# Channel.net
KiCad netlist of a schematic drawn in Altium Designer
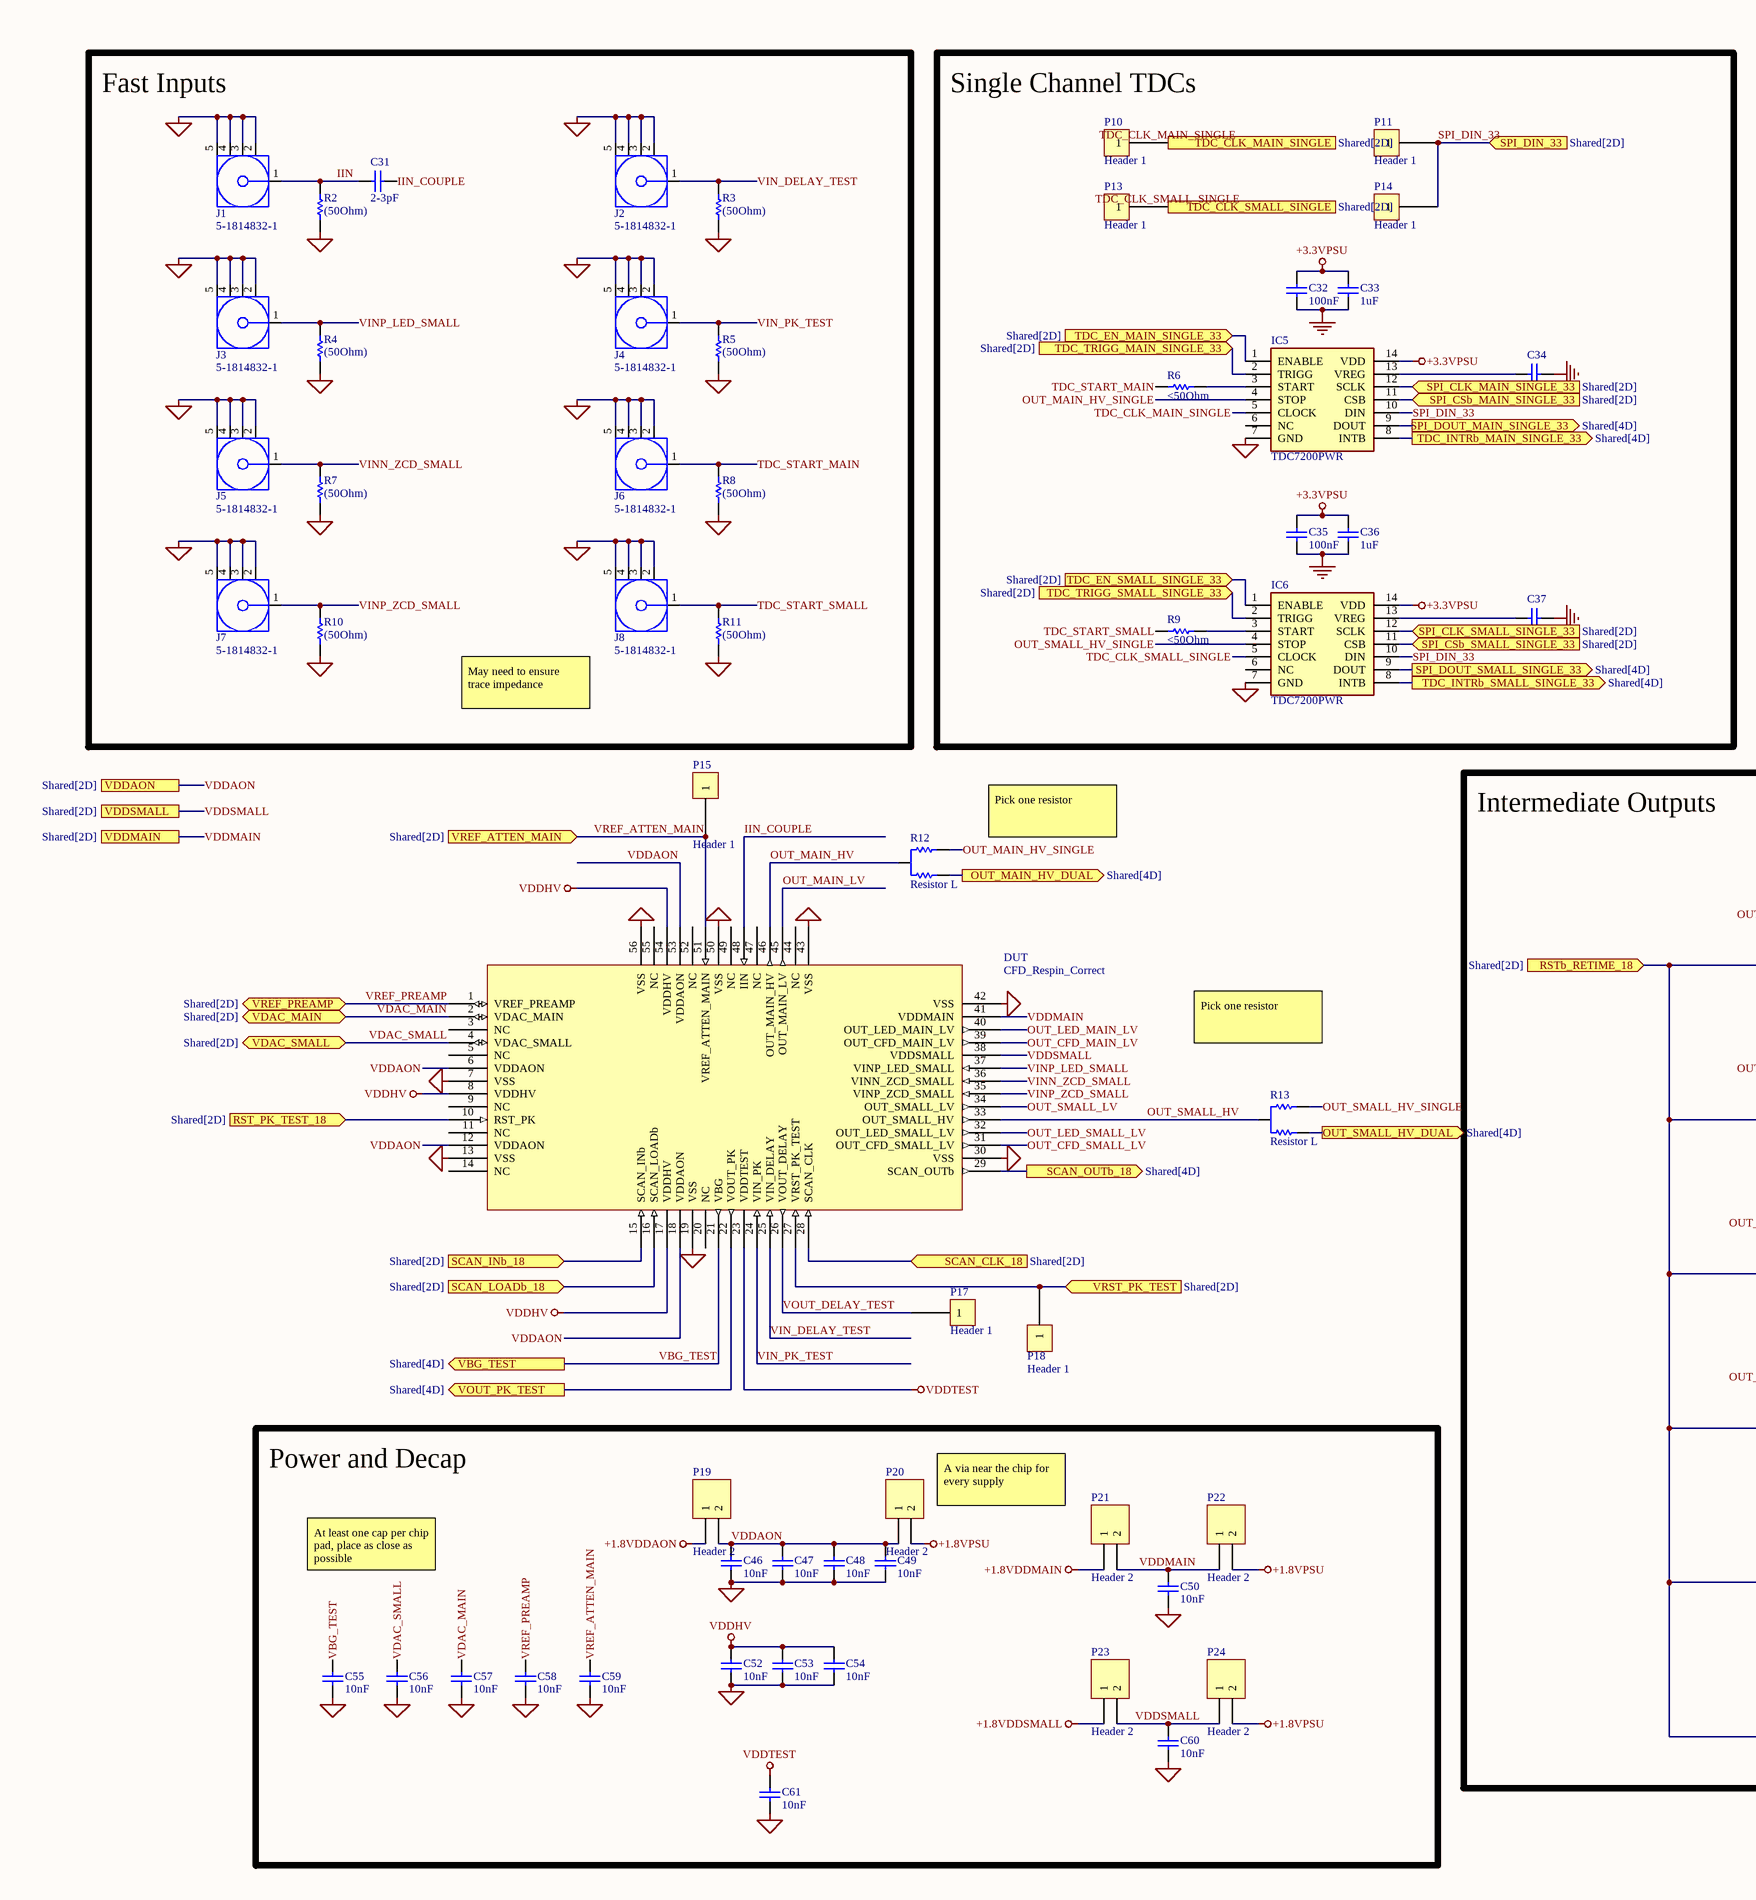
[diagram p0: Channel.SchDoc, left]
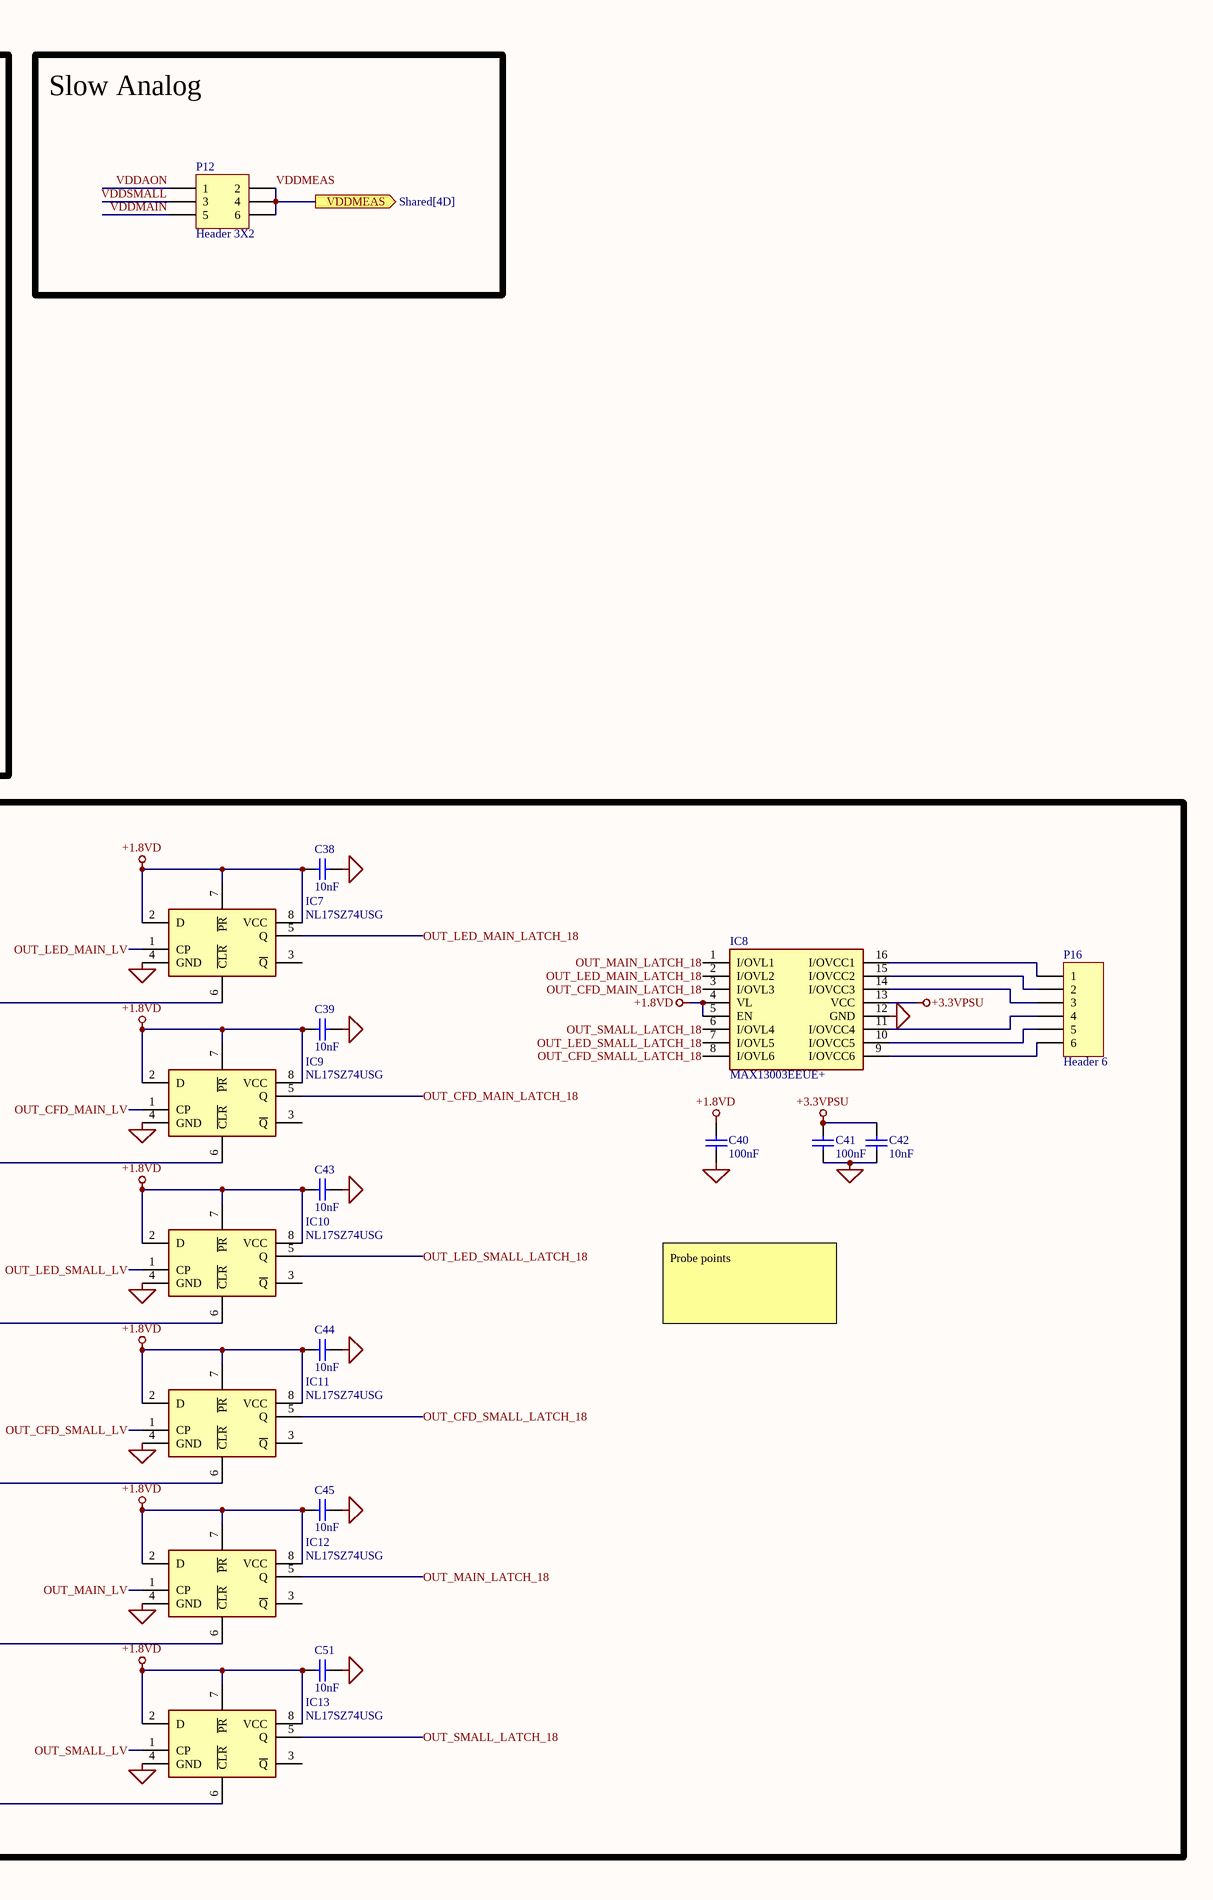
[diagram p1: Channel.SchDoc, right]

(export (version "E")
  (design (tool "Eeschema 10.0.6"))
  (components
    (comp (ref "C31")
      (value "2-3pF")
      (footprint "CAPC1608X90X35ML10T15")
      (description "0603,2-3pF")
      (fields (field (name "MANUFACTURER") "Murata"))
      (libsource (lib "Altium Content Vault") (part "CAP-NP-2"))
    )
    (comp (ref "C32")
      (value "100nF")
      (footprint "CAPC1608X90X35ML10T15")
      (description "0603,100nF")
      (fields (field (name "MANUFACTURER") "Murata"))
      (libsource (lib "Altium Content Vault") (part "CAP-NP-2"))
    )
    (comp (ref "C33")
      (value "1uF")
      (footprint "CAPC1608X90X35ML10T15")
      (description "0603,1uF")
      (fields (field (name "MANUFACTURER") "Murata"))
      (libsource (lib "Altium Content Vault") (part "CAP-NP-2"))
    )
    (comp (ref "C34")
      (value "1uF")
      (footprint "CAPC1608X90X35ML10T15")
      (description "0603,1uF")
      (fields (field (name "MANUFACTURER") "Murata"))
      (libsource (lib "Altium Content Vault") (part "CAP-NP-2"))
    )
    (comp (ref "C35")
      (value "100nF")
      (footprint "CAPC1608X90X35ML10T15")
      (description "0603,100nF")
      (fields (field (name "MANUFACTURER") "Murata"))
      (libsource (lib "Altium Content Vault") (part "CAP-NP-2"))
    )
    (comp (ref "C36")
      (value "1uF")
      (footprint "CAPC1608X90X35ML10T15")
      (description "0603,1uF")
      (fields (field (name "MANUFACTURER") "Murata"))
      (libsource (lib "Altium Content Vault") (part "CAP-NP-2"))
    )
    (comp (ref "C37")
      (value "1uF")
      (footprint "CAPC1608X90X35ML10T15")
      (description "0603,1uF")
      (fields (field (name "MANUFACTURER") "Murata"))
      (libsource (lib "Altium Content Vault") (part "CAP-NP-2"))
    )
    (comp (ref "C38")
      (value "10nF")
      (footprint "CAPC1608X90X35ML10T15")
      (description "0603,10nF")
      (fields (field (name "MANUFACTURER") "Murata"))
      (libsource (lib "Altium Content Vault") (part "CAP-NP-2"))
    )
    (comp (ref "C39")
      (value "10nF")
      (footprint "CAPC1608X90X35ML10T15")
      (description "0603,10nF")
      (fields (field (name "MANUFACTURER") "Murata"))
      (libsource (lib "Altium Content Vault") (part "CAP-NP-2"))
    )
    (comp (ref "C40")
      (value "100nF")
      (footprint "CAPC1608X90X35ML10T15")
      (description "0603,100nF")
      (fields (field (name "MANUFACTURER") "Murata"))
      (libsource (lib "Altium Content Vault") (part "CAP-NP-2"))
    )
    (comp (ref "C41")
      (value "100nF")
      (footprint "CAPC1608X90X35ML10T15")
      (description "0603,100nF")
      (fields (field (name "MANUFACTURER") "Murata"))
      (libsource (lib "Altium Content Vault") (part "CAP-NP-2"))
    )
    (comp (ref "C42")
      (value "10nF")
      (footprint "CAPC1608X90X35ML10T15")
      (description "0603,10nF")
      (fields (field (name "MANUFACTURER") "Murata"))
      (libsource (lib "Altium Content Vault") (part "CAP-NP-2"))
    )
    (comp (ref "C43")
      (value "10nF")
      (footprint "CAPC1608X90X35ML10T15")
      (description "0603,10nF")
      (fields (field (name "MANUFACTURER") "Murata"))
      (libsource (lib "Altium Content Vault") (part "CAP-NP-2"))
    )
    (comp (ref "C44")
      (value "10nF")
      (footprint "CAPC1608X90X35ML10T15")
      (description "0603,10nF")
      (fields (field (name "MANUFACTURER") "Murata"))
      (libsource (lib "Altium Content Vault") (part "CAP-NP-2"))
    )
    (comp (ref "C45")
      (value "10nF")
      (footprint "CAPC1608X90X35ML10T15")
      (description "0603,10nF")
      (fields (field (name "MANUFACTURER") "Murata"))
      (libsource (lib "Altium Content Vault") (part "CAP-NP-2"))
    )
    (comp (ref "C46")
      (value "10nF")
      (footprint "CAPC1608X90X35ML10T15")
      (description "0603,10nF")
      (fields (field (name "MANUFACTURER") "Murata"))
      (libsource (lib "Altium Content Vault") (part "CAP-NP-2"))
    )
    (comp (ref "C47")
      (value "10nF")
      (footprint "CAPC1608X90X35ML10T15")
      (description "0603,10nF")
      (fields (field (name "MANUFACTURER") "Murata"))
      (libsource (lib "Altium Content Vault") (part "CAP-NP-2"))
    )
    (comp (ref "C48")
      (value "10nF")
      (footprint "CAPC1608X90X35ML10T15")
      (description "0603,10nF")
      (fields (field (name "MANUFACTURER") "Murata"))
      (libsource (lib "Altium Content Vault") (part "CAP-NP-2"))
    )
    (comp (ref "C49")
      (value "10nF")
      (footprint "CAPC1608X90X35ML10T15")
      (description "0603,10nF")
      (fields (field (name "MANUFACTURER") "Murata"))
      (libsource (lib "Altium Content Vault") (part "CAP-NP-2"))
    )
    (comp (ref "C50")
      (value "10nF")
      (footprint "CAPC1608X90X35ML10T15")
      (description "0603,10nF")
      (fields (field (name "MANUFACTURER") "Murata"))
      (libsource (lib "Altium Content Vault") (part "CAP-NP-2"))
    )
    (comp (ref "C51")
      (value "10nF")
      (footprint "CAPC1608X90X35ML10T15")
      (description "0603,10nF")
      (fields (field (name "MANUFACTURER") "Murata"))
      (libsource (lib "Altium Content Vault") (part "CAP-NP-2"))
    )
    (comp (ref "C52")
      (value "10nF")
      (footprint "CAPC1608X90X35ML10T15")
      (description "0603,10nF")
      (fields (field (name "MANUFACTURER") "Murata"))
      (libsource (lib "Altium Content Vault") (part "CAP-NP-2"))
    )
    (comp (ref "C53")
      (value "10nF")
      (footprint "CAPC1608X90X35ML10T15")
      (description "0603,10nF")
      (fields (field (name "MANUFACTURER") "Murata"))
      (libsource (lib "Altium Content Vault") (part "CAP-NP-2"))
    )
    (comp (ref "C54")
      (value "10nF")
      (footprint "CAPC1608X90X35ML10T15")
      (description "0603,10nF")
      (fields (field (name "MANUFACTURER") "Murata"))
      (libsource (lib "Altium Content Vault") (part "CAP-NP-2"))
    )
    (comp (ref "C55")
      (value "10nF")
      (footprint "CAPC1608X90X35ML10T15")
      (description "0603,10nF")
      (fields (field (name "MANUFACTURER") "Murata"))
      (libsource (lib "Altium Content Vault") (part "CAP-NP-2"))
    )
    (comp (ref "C56")
      (value "10nF")
      (footprint "CAPC1608X90X35ML10T15")
      (description "0603,10nF")
      (fields (field (name "MANUFACTURER") "Murata"))
      (libsource (lib "Altium Content Vault") (part "CAP-NP-2"))
    )
    (comp (ref "C57")
      (value "10nF")
      (footprint "CAPC1608X90X35ML10T15")
      (description "0603,10nF")
      (fields (field (name "MANUFACTURER") "Murata"))
      (libsource (lib "Altium Content Vault") (part "CAP-NP-2"))
    )
    (comp (ref "C58")
      (value "10nF")
      (footprint "CAPC1608X90X35ML10T15")
      (description "0603,10nF")
      (fields (field (name "MANUFACTURER") "Murata"))
      (libsource (lib "Altium Content Vault") (part "CAP-NP-2"))
    )
    (comp (ref "C59")
      (value "10nF")
      (footprint "CAPC1608X90X35ML10T15")
      (description "0603,10nF")
      (fields (field (name "MANUFACTURER") "Murata"))
      (libsource (lib "Altium Content Vault") (part "CAP-NP-2"))
    )
    (comp (ref "C60")
      (value "10nF")
      (footprint "CAPC1608X90X35ML10T15")
      (description "0603,10nF")
      (fields (field (name "MANUFACTURER") "Murata"))
      (libsource (lib "Altium Content Vault") (part "CAP-NP-2"))
    )
    (comp (ref "C61")
      (value "10nF")
      (footprint "CAPC1608X90X35ML10T15")
      (description "0603,10nF")
      (fields (field (name "MANUFACTURER") "Murata"))
      (libsource (lib "Altium Content Vault") (part "CAP-NP-2"))
    )
    (comp (ref "DUT")
      (value "CFD_Respin_Correct")
      (footprint "QFN50P800X800X80_HS-57N_WIDEVIAS")
      (libsource (lib "intlib") (part "CFD_Respin_Correct"))
    )
    (comp (ref "IC5")
      (value "TDC7200PWR")
      (footprint "SamacSys:SOP65P640X120-14N")
      (description "Integrated Circuit")
      (libsource (lib "*") (part "TDC7200PWR"))
    )
    (comp (ref "IC6")
      (value "TDC7200PWR")
      (footprint "SamacSys:SOP65P640X120-14N")
      (description "Integrated Circuit")
      (libsource (lib "*") (part "TDC7200PWR"))
    )
    (comp (ref "IC7")
      (value "NL17SZ74USG")
      (footprint "SamacSys:SOP50P310X90-8N")
      (description "Flip Flops 1.65-5.5V CMOS Single D-Type")
      (libsource (lib "SamacSys") (part "NL17SZ74USG"))
    )
    (comp (ref "IC8")
      (value "MAX13003EEUE+")
      (footprint "SamacSys:SOP65P640X110-16N")
      (description "Integrated Circuit")
      (libsource (lib "*") (part "MAX13003EEUE+"))
    )
    (comp (ref "IC9")
      (value "NL17SZ74USG")
      (footprint "SamacSys:SOP50P310X90-8N")
      (description "Flip Flops 1.65-5.5V CMOS Single D-Type")
      (libsource (lib "SamacSys") (part "NL17SZ74USG"))
    )
    (comp (ref "IC10")
      (value "NL17SZ74USG")
      (footprint "SamacSys:SOP50P310X90-8N")
      (description "Flip Flops 1.65-5.5V CMOS Single D-Type")
      (libsource (lib "SamacSys") (part "NL17SZ74USG"))
    )
    (comp (ref "IC11")
      (value "NL17SZ74USG")
      (footprint "SamacSys:SOP50P310X90-8N")
      (description "Flip Flops 1.65-5.5V CMOS Single D-Type")
      (libsource (lib "SamacSys") (part "NL17SZ74USG"))
    )
    (comp (ref "IC12")
      (value "NL17SZ74USG")
      (footprint "SamacSys:SOP50P310X90-8N")
      (description "Flip Flops 1.65-5.5V CMOS Single D-Type")
      (libsource (lib "SamacSys") (part "NL17SZ74USG"))
    )
    (comp (ref "IC13")
      (value "NL17SZ74USG")
      (footprint "SamacSys:SOP50P310X90-8N")
      (description "Flip Flops 1.65-5.5V CMOS Single D-Type")
      (libsource (lib "SamacSys") (part "NL17SZ74USG"))
    )
    (comp (ref "J1")
      (value "5-1814832-1")
      (footprint "TECO-5-1814832-1_V")
      (fields (field (name "MANUFACTURER") "TE Connectivity"))
      (libsource (lib "Altium Content Vault") (part "CN-S-4F-RF5"))
    )
    (comp (ref "J2")
      (value "5-1814832-1")
      (footprint "TECO-5-1814832-1_V")
      (fields (field (name "MANUFACTURER") "TE Connectivity"))
      (libsource (lib "Altium Content Vault") (part "CN-S-4F-RF5"))
    )
    (comp (ref "J3")
      (value "5-1814832-1")
      (footprint "TECO-5-1814832-1_V")
      (fields (field (name "MANUFACTURER") "TE Connectivity"))
      (libsource (lib "Altium Content Vault") (part "CN-S-4F-RF5"))
    )
    (comp (ref "J4")
      (value "5-1814832-1")
      (footprint "TECO-5-1814832-1_V")
      (fields (field (name "MANUFACTURER") "TE Connectivity"))
      (libsource (lib "Altium Content Vault") (part "CN-S-4F-RF5"))
    )
    (comp (ref "J5")
      (value "5-1814832-1")
      (footprint "TECO-5-1814832-1_V")
      (fields (field (name "MANUFACTURER") "TE Connectivity"))
      (libsource (lib "Altium Content Vault") (part "CN-S-4F-RF5"))
    )
    (comp (ref "J6")
      (value "5-1814832-1")
      (footprint "TECO-5-1814832-1_V")
      (fields (field (name "MANUFACTURER") "TE Connectivity"))
      (libsource (lib "Altium Content Vault") (part "CN-S-4F-RF5"))
    )
    (comp (ref "J7")
      (value "5-1814832-1")
      (footprint "TECO-5-1814832-1_V")
      (fields (field (name "MANUFACTURER") "TE Connectivity"))
      (libsource (lib "Altium Content Vault") (part "CN-S-4F-RF5"))
    )
    (comp (ref "J8")
      (value "5-1814832-1")
      (footprint "TECO-5-1814832-1_V")
      (fields (field (name "MANUFACTURER") "TE Connectivity"))
      (libsource (lib "Altium Content Vault") (part "CN-S-4F-RF5"))
    )
    (comp (ref "P10") (value "Header 1") (footprint "Header1") (libsource (lib "") (part "Header 1_1")))
    (comp (ref "P11") (value "Header 1") (footprint "Header1") (libsource (lib "") (part "Header 1_1")))
    (comp (ref "P12")
      (value "Header 3X2")
      (footprint "HDR2X3")
      (description "Header, 3-Pin, Dual row")
      (fields (field (name "PUBLISHER") "Altium Limited"))
      (libsource (lib "Miscellaneous Connectors") (part "Header 3X2"))
    )
    (comp (ref "P13") (value "Header 1") (footprint "Header1") (libsource (lib "") (part "Header 1_1")))
    (comp (ref "P14") (value "Header 1") (footprint "Header1") (libsource (lib "") (part "Header 1_1")))
    (comp (ref "P15") (value "Header 1") (footprint "Header1") (libsource (lib "intlib") (part "Header 1")))
    (comp (ref "P16")
      (value "Header 6")
      (footprint "HDR1X6")
      (description "Header, 6-Pin")
      (fields (field (name "PUBLISHER") "Altium Limited"))
      (libsource (lib "Miscellaneous Connectors") (part "Header 6"))
    )
    (comp (ref "P17") (value "Header 1") (footprint "Header1") (libsource (lib "") (part "Header 1_2")))
    (comp (ref "P18") (value "Header 1") (footprint "Header1") (libsource (lib "") (part "Header 1_3")))
    (comp (ref "P19")
      (value "Header 2")
      (footprint "HDR1X2")
      (description "Header, 2-Pin")
      (fields (field (name "PUBLISHER") "Altium Limited"))
      (libsource (lib "Miscellaneous Connectors") (part "Header 2"))
    )
    (comp (ref "P20")
      (value "Header 2")
      (footprint "HDR1X2")
      (description "Header, 2-Pin")
      (fields (field (name "PUBLISHER") "Altium Limited"))
      (libsource (lib "Miscellaneous Connectors") (part "Header 2"))
    )
    (comp (ref "P21")
      (value "Header 2")
      (footprint "HDR1X2")
      (description "Header, 2-Pin")
      (fields (field (name "PUBLISHER") "Altium Limited"))
      (libsource (lib "Miscellaneous Connectors") (part "Header 2"))
    )
    (comp (ref "P22")
      (value "Header 2")
      (footprint "HDR1X2")
      (description "Header, 2-Pin")
      (fields (field (name "PUBLISHER") "Altium Limited"))
      (libsource (lib "Miscellaneous Connectors") (part "Header 2"))
    )
    (comp (ref "P23")
      (value "Header 2")
      (footprint "HDR1X2")
      (description "Header, 2-Pin")
      (fields (field (name "PUBLISHER") "Altium Limited"))
      (libsource (lib "Miscellaneous Connectors") (part "Header 2"))
    )
    (comp (ref "P24")
      (value "Header 2")
      (footprint "HDR1X2")
      (description "Header, 2-Pin")
      (fields (field (name "PUBLISHER") "Altium Limited"))
      (libsource (lib "Miscellaneous Connectors") (part "Header 2"))
    )
    (comp (ref "R2")
      (value "(50Ohm)")
      (footprint "RESC1609X50X30NL8T20")
      (description "0603,(50Ohm),Do Not Populate")
      (fields (field (name "MANUFACTURER") "Vishay Semiconductor"))
      (libsource (lib "Altium Content Vault") (part "RES-2"))
    )
    (comp (ref "R3")
      (value "(50Ohm)")
      (footprint "RESC1609X50X30NL8T20")
      (description "0603,(50Ohm),Do Not Populate")
      (fields (field (name "MANUFACTURER") "Vishay Semiconductor"))
      (libsource (lib "Altium Content Vault") (part "RES-2"))
    )
    (comp (ref "R4")
      (value "(50Ohm)")
      (footprint "RESC1609X50X30NL8T20")
      (description "0603,(50Ohm),Do Not Populate")
      (fields (field (name "MANUFACTURER") "Vishay Semiconductor"))
      (libsource (lib "Altium Content Vault") (part "RES-2"))
    )
    (comp (ref "R5")
      (value "(50Ohm)")
      (footprint "RESC1609X50X30NL8T20")
      (description "0603,(50Ohm),Do Not Populate")
      (fields (field (name "MANUFACTURER") "Vishay Semiconductor"))
      (libsource (lib "Altium Content Vault") (part "RES-2"))
    )
    (comp (ref "R6")
      (value "<50Ohm")
      (footprint "RESC1609X50X30NL8T20")
      (description "0603,<50Ohm")
      (fields (field (name "MANUFACTURER") "Vishay Semiconductor"))
      (libsource (lib "Altium Content Vault") (part "RES-2"))
    )
    (comp (ref "R7")
      (value "(50Ohm)")
      (footprint "RESC1609X50X30NL8T20")
      (description "0603,(50Ohm),Do Not Populate")
      (fields (field (name "MANUFACTURER") "Vishay Semiconductor"))
      (libsource (lib "Altium Content Vault") (part "RES-2"))
    )
    (comp (ref "R8")
      (value "(50Ohm)")
      (footprint "RESC1609X50X30NL8T20")
      (description "0603,(50Ohm),Do Not Populate")
      (fields (field (name "MANUFACTURER") "Vishay Semiconductor"))
      (libsource (lib "Altium Content Vault") (part "RES-2"))
    )
    (comp (ref "R9")
      (value "<50Ohm")
      (footprint "RESC1609X50X30NL8T20")
      (description "0603,<50Ohm")
      (fields (field (name "MANUFACTURER") "Vishay Semiconductor"))
      (libsource (lib "Altium Content Vault") (part "RES-2"))
    )
    (comp (ref "R10")
      (value "(50Ohm)")
      (footprint "RESC1609X50X30NL8T20")
      (description "0603,(50Ohm),Do Not Populate")
      (fields (field (name "MANUFACTURER") "Vishay Semiconductor"))
      (libsource (lib "Altium Content Vault") (part "RES-2"))
    )
    (comp (ref "R11")
      (value "(50Ohm)")
      (footprint "RESC1609X50X30NL8T20")
      (description "0603,(50Ohm),Do Not Populate")
      (fields (field (name "MANUFACTURER") "Vishay Semiconductor"))
      (libsource (lib "Altium Content Vault") (part "RES-2"))
    )
    (comp (ref "R12")
      (value "Resistor L")
      (footprint "RESL")
      (description "Pick one 0603,0Ohm")
      (libsource (lib "intlib") (part "Resistor L"))
    )
    (comp (ref "R13")
      (value "Resistor L")
      (footprint "RESL")
      (description "Pick one 0603,0Ohm")
      (libsource (lib "intlib") (part "Resistor L"))
    )
  )
  (nets
    (net (code "1") (name "+1.8VD") (class "Default")
      (node (ref "C38") (pin "2") (pinfunction "2_2") (pintype "passive"))
      (node (ref "C39") (pin "2") (pinfunction "2_2") (pintype "passive"))
      (node (ref "C40") (pin "2") (pinfunction "2_2") (pintype "passive"))
      (node (ref "C43") (pin "2") (pinfunction "2_2") (pintype "passive"))
      (node (ref "C44") (pin "2") (pinfunction "2_2") (pintype "passive"))
      (node (ref "C45") (pin "2") (pinfunction "2_2") (pintype "passive"))
      (node (ref "C51") (pin "2") (pinfunction "2_2") (pintype "passive"))
      (node (ref "IC10") (pin "2") (pinfunction "D_2") (pintype "passive"))
      (node (ref "IC10") (pin "7") (pinfunction "~{PR}_7") (pintype "passive"))
      (node (ref "IC10") (pin "8") (pinfunction "VCC_8") (pintype "passive"))
      (node (ref "IC11") (pin "2") (pinfunction "D_2") (pintype "passive"))
      (node (ref "IC11") (pin "7") (pinfunction "~{PR}_7") (pintype "passive"))
      (node (ref "IC11") (pin "8") (pinfunction "VCC_8") (pintype "passive"))
      (node (ref "IC12") (pin "2") (pinfunction "D_2") (pintype "passive"))
      (node (ref "IC12") (pin "7") (pinfunction "~{PR}_7") (pintype "passive"))
      (node (ref "IC12") (pin "8") (pinfunction "VCC_8") (pintype "passive"))
      (node (ref "IC13") (pin "2") (pinfunction "D_2") (pintype "passive"))
      (node (ref "IC13") (pin "7") (pinfunction "~{PR}_7") (pintype "passive"))
      (node (ref "IC13") (pin "8") (pinfunction "VCC_8") (pintype "passive"))
      (node (ref "IC7") (pin "2") (pinfunction "D_2") (pintype "passive"))
      (node (ref "IC7") (pin "7") (pinfunction "~{PR}_7") (pintype "passive"))
      (node (ref "IC7") (pin "8") (pinfunction "VCC_8") (pintype "passive"))
      (node (ref "IC8") (pin "4") (pinfunction "VL_4") (pintype "passive"))
      (node (ref "IC8") (pin "5") (pinfunction "EN_5") (pintype "passive"))
      (node (ref "IC9") (pin "2") (pinfunction "D_2") (pintype "passive"))
      (node (ref "IC9") (pin "7") (pinfunction "~{PR}_7") (pintype "passive"))
      (node (ref "IC9") (pin "8") (pinfunction "VCC_8") (pintype "passive"))
    )
    (net (code "2") (name "+1.8VDDAON") (class "Default")
      (node (ref "P19") (pin "1") (pinfunction "1_1") (pintype "passive"))
    )
    (net (code "3") (name "+1.8VDDMAIN") (class "Default")
      (node (ref "P21") (pin "1") (pinfunction "1_1") (pintype "passive"))
    )
    (net (code "4") (name "+1.8VDDSMALL") (class "Default")
      (node (ref "P23") (pin "1") (pinfunction "1_1") (pintype "passive"))
    )
    (net (code "5") (name "+1.8VPSU") (class "Default")
      (node (ref "P20") (pin "2") (pinfunction "2_2") (pintype "passive"))
      (node (ref "P22") (pin "2") (pinfunction "2_2") (pintype "passive"))
      (node (ref "P24") (pin "2") (pinfunction "2_2") (pintype "passive"))
    )
    (net (code "6") (name "+3.3VPSU") (class "Default")
      (node (ref "C32") (pin "1") (pinfunction "1_1") (pintype "passive"))
      (node (ref "C33") (pin "1") (pinfunction "1_1") (pintype "passive"))
      (node (ref "C35") (pin "1") (pinfunction "1_1") (pintype "passive"))
      (node (ref "C36") (pin "1") (pinfunction "1_1") (pintype "passive"))
      (node (ref "C41") (pin "2") (pinfunction "2_2") (pintype "passive"))
      (node (ref "C42") (pin "2") (pinfunction "2_2") (pintype "passive"))
      (node (ref "IC5") (pin "14") (pinfunction "VDD_14") (pintype "passive"))
      (node (ref "IC6") (pin "14") (pinfunction "VDD_14") (pintype "passive"))
      (node (ref "IC8") (pin "13") (pinfunction "VCC_13") (pintype "passive"))
    )
    (net (code "7") (name "/IIN") (class "Default")
      (node (ref "C31") (pin "1") (pinfunction "1_1") (pintype "passive"))
      (node (ref "J1") (pin "1") (pinfunction "1_1") (pintype "passive"))
      (node (ref "R2") (pin "2") (pinfunction "2_2") (pintype "passive"))
    )
    (net (code "8") (name "/IIN_COUPLE") (class "Default")
      (node (ref "C31") (pin "2") (pinfunction "2_2") (pintype "passive"))
      (node (ref "DUT") (pin "48") (pinfunction "IIN_48") (pintype "input"))
    )
    (net (code "9") (name "/OUT_CFD_MAIN_LATCH_18") (class "Default")
      (node (ref "IC8") (pin "3") (pinfunction "I/OVL3_3") (pintype "passive"))
      (node (ref "IC9") (pin "5") (pinfunction "Q_5") (pintype "passive"))
    )
    (net (code "10") (name "/OUT_CFD_MAIN_LV") (class "Default")
      (node (ref "DUT") (pin "39") (pinfunction "OUT_CFD_MAIN_LV_39") (pintype "output"))
      (node (ref "IC9") (pin "1") (pinfunction "CP_1") (pintype "passive"))
    )
    (net (code "11") (name "/OUT_CFD_SMALL_LATCH_18") (class "Default")
      (node (ref "IC11") (pin "5") (pinfunction "Q_5") (pintype "passive"))
      (node (ref "IC8") (pin "8") (pinfunction "I/OVL6_8") (pintype "passive"))
    )
    (net (code "12") (name "/OUT_CFD_SMALL_LV") (class "Default")
      (node (ref "DUT") (pin "31") (pinfunction "OUT_CFD_SMALL_LV_31") (pintype "output"))
      (node (ref "IC11") (pin "1") (pinfunction "CP_1") (pintype "passive"))
    )
    (net (code "13") (name "/OUT_LED_MAIN_LATCH_18") (class "Default")
      (node (ref "IC7") (pin "5") (pinfunction "Q_5") (pintype "passive"))
      (node (ref "IC8") (pin "2") (pinfunction "I/OVL2_2") (pintype "passive"))
    )
    (net (code "14") (name "/OUT_LED_MAIN_LV") (class "Default")
      (node (ref "DUT") (pin "40") (pinfunction "OUT_LED_MAIN_LV_40") (pintype "output"))
      (node (ref "IC7") (pin "1") (pinfunction "CP_1") (pintype "passive"))
    )
    (net (code "15") (name "/OUT_LED_SMALL_LATCH_18") (class "Default")
      (node (ref "IC10") (pin "5") (pinfunction "Q_5") (pintype "passive"))
      (node (ref "IC8") (pin "7") (pinfunction "I/OVL5_7") (pintype "passive"))
    )
    (net (code "16") (name "/OUT_LED_SMALL_LV") (class "Default")
      (node (ref "DUT") (pin "32") (pinfunction "OUT_LED_SMALL_LV_32") (pintype "output"))
      (node (ref "IC10") (pin "1") (pinfunction "CP_1") (pintype "passive"))
    )
    (net (code "17") (name "/OUT_MAIN_HV") (class "Default")
      (node (ref "DUT") (pin "46") (pinfunction "OUT_MAIN_HV_46") (pintype "output"))
      (node (ref "R12") (pin "1") (pinfunction "1_1") (pintype "passive"))
    )
    (net (code "18") (name "/OUT_MAIN_HV_DUAL") (class "Default")
      (node (ref "R12") (pin "2") (pinfunction "2_2") (pintype "passive"))
    )
    (net (code "19") (name "/OUT_MAIN_HV_SINGLE") (class "Default")
      (node (ref "IC5") (pin "4") (pinfunction "STOP_4") (pintype "passive"))
      (node (ref "R12") (pin "3") (pinfunction "3_3") (pintype "passive"))
    )
    (net (code "20") (name "/OUT_MAIN_LATCH_18") (class "Default")
      (node (ref "IC12") (pin "5") (pinfunction "Q_5") (pintype "passive"))
      (node (ref "IC8") (pin "1") (pinfunction "I/OVL1_1") (pintype "passive"))
    )
    (net (code "21") (name "/OUT_MAIN_LV") (class "Default")
      (node (ref "DUT") (pin "45") (pinfunction "OUT_MAIN_LV_45") (pintype "output"))
      (node (ref "IC12") (pin "1") (pinfunction "CP_1") (pintype "passive"))
    )
    (net (code "22") (name "/OUT_SMALL_HV") (class "Default")
      (node (ref "DUT") (pin "33") (pinfunction "OUT_SMALL_HV_33") (pintype "output"))
      (node (ref "R13") (pin "1") (pinfunction "1_1") (pintype "passive"))
    )
    (net (code "23") (name "/OUT_SMALL_HV_DUAL") (class "Default")
      (node (ref "R13") (pin "2") (pinfunction "2_2") (pintype "passive"))
    )
    (net (code "24") (name "/OUT_SMALL_HV_SINGLE") (class "Default")
      (node (ref "IC6") (pin "4") (pinfunction "STOP_4") (pintype "passive"))
      (node (ref "R13") (pin "3") (pinfunction "3_3") (pintype "passive"))
    )
    (net (code "25") (name "/OUT_SMALL_LATCH_18") (class "Default")
      (node (ref "IC13") (pin "5") (pinfunction "Q_5") (pintype "passive"))
      (node (ref "IC8") (pin "6") (pinfunction "I/OVL4_6") (pintype "passive"))
    )
    (net (code "26") (name "/OUT_SMALL_LV") (class "Default")
      (node (ref "DUT") (pin "34") (pinfunction "OUT_SMALL_LV_34") (pintype "output"))
      (node (ref "IC13") (pin "1") (pinfunction "CP_1") (pintype "passive"))
    )
    (net (code "27") (name "/RST_PK_TEST_18") (class "Default")
      (node (ref "DUT") (pin "10") (pinfunction "RST_PK_10") (pintype "input"))
    )
    (net (code "28") (name "/RSTb_RETIME_18") (class "Default")
      (node (ref "IC10") (pin "6") (pinfunction "~{CLR}_6") (pintype "passive"))
      (node (ref "IC11") (pin "6") (pinfunction "~{CLR}_6") (pintype "passive"))
      (node (ref "IC12") (pin "6") (pinfunction "~{CLR}_6") (pintype "passive"))
      (node (ref "IC13") (pin "6") (pinfunction "~{CLR}_6") (pintype "passive"))
      (node (ref "IC7") (pin "6") (pinfunction "~{CLR}_6") (pintype "passive"))
      (node (ref "IC9") (pin "6") (pinfunction "~{CLR}_6") (pintype "passive"))
    )
    (net (code "29") (name "/SCAN_CLK_18") (class "Default")
      (node (ref "DUT") (pin "28") (pinfunction "SCAN_CLK_28") (pintype "input"))
    )
    (net (code "30") (name "/SCAN_INb_18") (class "Default")
      (node (ref "DUT") (pin "15") (pinfunction "SCAN_INb_15") (pintype "input"))
    )
    (net (code "31") (name "/SCAN_LOADb_18") (class "Default")
      (node (ref "DUT") (pin "16") (pinfunction "SCAN_LOADb_16") (pintype "input"))
    )
    (net (code "32") (name "/SCAN_OUTb_18") (class "Default")
      (node (ref "DUT") (pin "29") (pinfunction "SCAN_OUTb_29") (pintype "output"))
    )
    (net (code "33") (name "/SPI_CLK_MAIN_SINGLE_33") (class "Default")
      (node (ref "IC5") (pin "12") (pinfunction "SCLK_12") (pintype "passive"))
    )
    (net (code "34") (name "/SPI_CLK_SMALL_SINGLE_33") (class "Default")
      (node (ref "IC6") (pin "12") (pinfunction "SCLK_12") (pintype "passive"))
    )
    (net (code "35") (name "/SPI_CSb_MAIN_SINGLE_33") (class "Default")
      (node (ref "IC5") (pin "11") (pinfunction "CSB_11") (pintype "passive"))
    )
    (net (code "36") (name "/SPI_CSb_SMALL_SINGLE_33") (class "Default")
      (node (ref "IC6") (pin "11") (pinfunction "CSB_11") (pintype "passive"))
    )
    (net (code "37") (name "/SPI_DIN_33") (class "Default")
      (node (ref "IC5") (pin "10") (pinfunction "DIN_10") (pintype "passive"))
      (node (ref "IC6") (pin "10") (pinfunction "DIN_10") (pintype "passive"))
      (node (ref "P11") (pin "1") (pinfunction "1_1") (pintype "passive"))
      (node (ref "P14") (pin "1") (pinfunction "1_1") (pintype "passive"))
    )
    (net (code "38") (name "/SPI_DOUT_MAIN_SINGLE_33") (class "Default")
      (node (ref "IC5") (pin "9") (pinfunction "DOUT_9") (pintype "passive"))
    )
    (net (code "39") (name "/SPI_DOUT_SMALL_SINGLE_33") (class "Default")
      (node (ref "IC6") (pin "9") (pinfunction "DOUT_9") (pintype "passive"))
    )
    (net (code "40") (name "/TDC_CLK_MAIN_SINGLE") (class "Default")
      (node (ref "IC5") (pin "5") (pinfunction "CLOCK_5") (pintype "passive"))
      (node (ref "P10") (pin "1") (pinfunction "1_1") (pintype "passive"))
    )
    (net (code "41") (name "/TDC_CLK_SMALL_SINGLE") (class "Default")
      (node (ref "IC6") (pin "5") (pinfunction "CLOCK_5") (pintype "passive"))
      (node (ref "P13") (pin "1") (pinfunction "1_1") (pintype "passive"))
    )
    (net (code "42") (name "/TDC_EN_MAIN_SINGLE_33") (class "Default")
      (node (ref "IC5") (pin "1") (pinfunction "ENABLE_1") (pintype "passive"))
    )
    (net (code "43") (name "/TDC_EN_SMALL_SINGLE_33") (class "Default")
      (node (ref "IC6") (pin "1") (pinfunction "ENABLE_1") (pintype "passive"))
    )
    (net (code "44") (name "/TDC_INTRb_MAIN_SINGLE_33") (class "Default")
      (node (ref "IC5") (pin "8") (pinfunction "INTB_8") (pintype "passive"))
    )
    (net (code "45") (name "/TDC_INTRb_SMALL_SINGLE_33") (class "Default")
      (node (ref "IC6") (pin "8") (pinfunction "INTB_8") (pintype "passive"))
    )
    (net (code "46") (name "/TDC_START_MAIN") (class "Default")
      (node (ref "J6") (pin "1") (pinfunction "1_1") (pintype "passive"))
      (node (ref "R6") (pin "1") (pinfunction "1_1") (pintype "passive"))
      (node (ref "R8") (pin "2") (pinfunction "2_2") (pintype "passive"))
    )
    (net (code "47") (name "/TDC_START_SMALL") (class "Default")
      (node (ref "J8") (pin "1") (pinfunction "1_1") (pintype "passive"))
      (node (ref "R11") (pin "2") (pinfunction "2_2") (pintype "passive"))
      (node (ref "R9") (pin "1") (pinfunction "1_1") (pintype "passive"))
    )
    (net (code "48") (name "/TDC_TRIGG_MAIN_SINGLE_33") (class "Default")
      (node (ref "IC5") (pin "2") (pinfunction "TRIGG_2") (pintype "passive"))
    )
    (net (code "49") (name "/TDC_TRIGG_SMALL_SINGLE_33") (class "Default")
      (node (ref "IC6") (pin "2") (pinfunction "TRIGG_2") (pintype "passive"))
    )
    (net (code "50") (name "/VBG_TEST") (class "Default")
      (node (ref "C55") (pin "2") (pinfunction "2_2") (pintype "passive"))
      (node (ref "DUT") (pin "21") (pinfunction "VBG_21") (pintype "output"))
    )
    (net (code "51") (name "/VDAC_MAIN") (class "Default")
      (node (ref "C57") (pin "2") (pinfunction "2_2") (pintype "passive"))
      (node (ref "DUT") (pin "2") (pinfunction "VDAC_MAIN_2") (pintype "bidirectional"))
    )
    (net (code "52") (name "/VDAC_SMALL") (class "Default")
      (node (ref "C56") (pin "2") (pinfunction "2_2") (pintype "passive"))
      (node (ref "DUT") (pin "4") (pinfunction "VDAC_SMALL_4") (pintype "bidirectional"))
    )
    (net (code "53") (name "/VDDAON") (class "Default")
      (node (ref "C46") (pin "2") (pinfunction "2_2") (pintype "passive"))
      (node (ref "C47") (pin "2") (pinfunction "2_2") (pintype "passive"))
      (node (ref "C48") (pin "2") (pinfunction "2_2") (pintype "passive"))
      (node (ref "C49") (pin "2") (pinfunction "2_2") (pintype "passive"))
      (node (ref "DUT") (pin "12") (pinfunction "VDDAON_12") (pintype "power_in"))
      (node (ref "DUT") (pin "18") (pinfunction "VDDAON_18") (pintype "power_in"))
      (node (ref "DUT") (pin "53") (pinfunction "VDDAON_53") (pintype "power_in"))
      (node (ref "DUT") (pin "6") (pinfunction "VDDAON_6") (pintype "power_in"))
      (node (ref "P12") (pin "1") (pinfunction "1_1") (pintype "passive"))
      (node (ref "P19") (pin "2") (pinfunction "2_2") (pintype "passive"))
      (node (ref "P20") (pin "1") (pinfunction "1_1") (pintype "passive"))
    )
    (net (code "54") (name "/VDDMAIN") (class "Default")
      (node (ref "C50") (pin "2") (pinfunction "2_2") (pintype "passive"))
      (node (ref "DUT") (pin "41") (pinfunction "VDDMAIN_41") (pintype "power_in"))
      (node (ref "P12") (pin "5") (pinfunction "5_5") (pintype "passive"))
      (node (ref "P21") (pin "2") (pinfunction "2_2") (pintype "passive"))
      (node (ref "P22") (pin "1") (pinfunction "1_1") (pintype "passive"))
    )
    (net (code "55") (name "/VDDMEAS") (class "Default")
      (node (ref "P12") (pin "2") (pinfunction "2_2") (pintype "passive"))
      (node (ref "P12") (pin "4") (pinfunction "4_4") (pintype "passive"))
      (node (ref "P12") (pin "6") (pinfunction "6_6") (pintype "passive"))
    )
    (net (code "56") (name "/VDDSMALL") (class "Default")
      (node (ref "C60") (pin "2") (pinfunction "2_2") (pintype "passive"))
      (node (ref "DUT") (pin "38") (pinfunction "VDDSMALL_38") (pintype "power_in"))
      (node (ref "P12") (pin "3") (pinfunction "3_3") (pintype "passive"))
      (node (ref "P23") (pin "2") (pinfunction "2_2") (pintype "passive"))
      (node (ref "P24") (pin "1") (pinfunction "1_1") (pintype "passive"))
    )
    (net (code "57") (name "/VINN_ZCD_SMALL") (class "Default")
      (node (ref "DUT") (pin "36") (pinfunction "VINN_ZCD_SMALL_36") (pintype "input"))
      (node (ref "J5") (pin "1") (pinfunction "1_1") (pintype "passive"))
      (node (ref "R7") (pin "2") (pinfunction "2_2") (pintype "passive"))
    )
    (net (code "58") (name "/VINP_LED_SMALL") (class "Default")
      (node (ref "DUT") (pin "37") (pinfunction "VINP_LED_SMALL_37") (pintype "input"))
      (node (ref "J3") (pin "1") (pinfunction "1_1") (pintype "passive"))
      (node (ref "R4") (pin "2") (pinfunction "2_2") (pintype "passive"))
    )
    (net (code "59") (name "/VINP_ZCD_SMALL") (class "Default")
      (node (ref "DUT") (pin "35") (pinfunction "VINP_ZCD_SMALL_35") (pintype "input"))
      (node (ref "J7") (pin "1") (pinfunction "1_1") (pintype "passive"))
      (node (ref "R10") (pin "2") (pinfunction "2_2") (pintype "passive"))
    )
    (net (code "60") (name "/VIN_DELAY_TEST") (class "Default")
      (node (ref "DUT") (pin "25") (pinfunction "VIN_DELAY_25") (pintype "input"))
      (node (ref "J2") (pin "1") (pinfunction "1_1") (pintype "passive"))
      (node (ref "R3") (pin "2") (pinfunction "2_2") (pintype "passive"))
    )
    (net (code "61") (name "/VIN_PK_TEST") (class "Default")
      (node (ref "DUT") (pin "24") (pinfunction "VIN_PK_24") (pintype "input"))
      (node (ref "J4") (pin "1") (pinfunction "1_1") (pintype "passive"))
      (node (ref "R5") (pin "2") (pinfunction "2_2") (pintype "passive"))
    )
    (net (code "62") (name "/VOUT_DELAY_TEST") (class "Default")
      (node (ref "DUT") (pin "26") (pinfunction "VOUT_DELAY_26") (pintype "output"))
      (node (ref "P17") (pin "1") (pinfunction "1_1") (pintype "passive"))
    )
    (net (code "63") (name "/VOUT_PK_TEST") (class "Default")
      (node (ref "DUT") (pin "22") (pinfunction "VOUT_PK_22") (pintype "output"))
    )
    (net (code "64") (name "/VREF_ATTEN_MAIN") (class "Default")
      (node (ref "C59") (pin "2") (pinfunction "2_2") (pintype "passive"))
      (node (ref "DUT") (pin "51") (pinfunction "VREF_ATTEN_MAIN_51") (pintype "input"))
      (node (ref "P15") (pin "1") (pinfunction "1_1") (pintype "passive"))
    )
    (net (code "65") (name "/VREF_PREAMP") (class "Default")
      (node (ref "C58") (pin "2") (pinfunction "2_2") (pintype "passive"))
      (node (ref "DUT") (pin "1") (pinfunction "VREF_PREAMP_1") (pintype "bidirectional"))
    )
    (net (code "66") (name "/VRST_PK_TEST") (class "Default")
      (node (ref "DUT") (pin "27") (pinfunction "VRST_PK_TEST_27") (pintype "input"))
      (node (ref "P18") (pin "1") (pinfunction "1_1") (pintype "passive"))
    )
    (net (code "67") (name "GND") (class "Default")
      (node (ref "C32") (pin "2") (pinfunction "2_2") (pintype "passive"))
      (node (ref "C33") (pin "2") (pinfunction "2_2") (pintype "passive"))
      (node (ref "C34") (pin "2") (pinfunction "2_2") (pintype "passive"))
      (node (ref "C35") (pin "2") (pinfunction "2_2") (pintype "passive"))
      (node (ref "C36") (pin "2") (pinfunction "2_2") (pintype "passive"))
      (node (ref "C37") (pin "2") (pinfunction "2_2") (pintype "passive"))
      (node (ref "C38") (pin "1") (pinfunction "1_1") (pintype "passive"))
      (node (ref "C39") (pin "1") (pinfunction "1_1") (pintype "passive"))
      (node (ref "C40") (pin "1") (pinfunction "1_1") (pintype "passive"))
      (node (ref "C41") (pin "1") (pinfunction "1_1") (pintype "passive"))
      (node (ref "C42") (pin "1") (pinfunction "1_1") (pintype "passive"))
      (node (ref "C43") (pin "1") (pinfunction "1_1") (pintype "passive"))
      (node (ref "C44") (pin "1") (pinfunction "1_1") (pintype "passive"))
      (node (ref "C45") (pin "1") (pinfunction "1_1") (pintype "passive"))
      (node (ref "C46") (pin "1") (pinfunction "1_1") (pintype "passive"))
      (node (ref "C47") (pin "1") (pinfunction "1_1") (pintype "passive"))
      (node (ref "C48") (pin "1") (pinfunction "1_1") (pintype "passive"))
      (node (ref "C49") (pin "1") (pinfunction "1_1") (pintype "passive"))
      (node (ref "C50") (pin "1") (pinfunction "1_1") (pintype "passive"))
      (node (ref "C51") (pin "1") (pinfunction "1_1") (pintype "passive"))
      (node (ref "C52") (pin "1") (pinfunction "1_1") (pintype "passive"))
      (node (ref "C53") (pin "1") (pinfunction "1_1") (pintype "passive"))
      (node (ref "C54") (pin "1") (pinfunction "1_1") (pintype "passive"))
      (node (ref "C55") (pin "1") (pinfunction "1_1") (pintype "passive"))
      (node (ref "C56") (pin "1") (pinfunction "1_1") (pintype "passive"))
      (node (ref "C57") (pin "1") (pinfunction "1_1") (pintype "passive"))
      (node (ref "C58") (pin "1") (pinfunction "1_1") (pintype "passive"))
      (node (ref "C59") (pin "1") (pinfunction "1_1") (pintype "passive"))
      (node (ref "C60") (pin "1") (pinfunction "1_1") (pintype "passive"))
      (node (ref "C61") (pin "1") (pinfunction "1_1") (pintype "passive"))
      (node (ref "DUT") (pin "13") (pinfunction "VSS_13") (pintype "power_in"))
      (node (ref "DUT") (pin "19") (pinfunction "VSS_19") (pintype "power_in"))
      (node (ref "DUT") (pin "30") (pinfunction "VSS_30") (pintype "power_in"))
      (node (ref "DUT") (pin "42") (pinfunction "VSS_42") (pintype "power_in"))
      (node (ref "DUT") (pin "43") (pinfunction "VSS_43") (pintype "power_in"))
      (node (ref "DUT") (pin "50") (pinfunction "VSS_50") (pintype "power_in"))
      (node (ref "DUT") (pin "56") (pinfunction "VSS_56") (pintype "power_in"))
      (node (ref "DUT") (pin "7") (pinfunction "VSS_7") (pintype "power_in"))
      (node (ref "IC10") (pin "4") (pinfunction "GND_4") (pintype "passive"))
      (node (ref "IC11") (pin "4") (pinfunction "GND_4") (pintype "passive"))
      (node (ref "IC12") (pin "4") (pinfunction "GND_4") (pintype "passive"))
      (node (ref "IC13") (pin "4") (pinfunction "GND_4") (pintype "passive"))
      (node (ref "IC5") (pin "7") (pinfunction "GND_7") (pintype "passive"))
      (node (ref "IC6") (pin "7") (pinfunction "GND_7") (pintype "passive"))
      (node (ref "IC7") (pin "4") (pinfunction "GND_4") (pintype "passive"))
      (node (ref "IC8") (pin "12") (pinfunction "GND_12") (pintype "passive"))
      (node (ref "IC9") (pin "4") (pinfunction "GND_4") (pintype "passive"))
      (node (ref "J1") (pin "2") (pinfunction "2_2") (pintype "passive"))
      (node (ref "J1") (pin "3") (pinfunction "3_3") (pintype "passive"))
      (node (ref "J1") (pin "4") (pinfunction "4_4") (pintype "passive"))
      (node (ref "J1") (pin "5") (pinfunction "5_5") (pintype "passive"))
      (node (ref "J2") (pin "2") (pinfunction "2_2") (pintype "passive"))
      (node (ref "J2") (pin "3") (pinfunction "3_3") (pintype "passive"))
      (node (ref "J2") (pin "4") (pinfunction "4_4") (pintype "passive"))
      (node (ref "J2") (pin "5") (pinfunction "5_5") (pintype "passive"))
      (node (ref "J3") (pin "2") (pinfunction "2_2") (pintype "passive"))
      (node (ref "J3") (pin "3") (pinfunction "3_3") (pintype "passive"))
      (node (ref "J3") (pin "4") (pinfunction "4_4") (pintype "passive"))
      (node (ref "J3") (pin "5") (pinfunction "5_5") (pintype "passive"))
      (node (ref "J4") (pin "2") (pinfunction "2_2") (pintype "passive"))
      (node (ref "J4") (pin "3") (pinfunction "3_3") (pintype "passive"))
      (node (ref "J4") (pin "4") (pinfunction "4_4") (pintype "passive"))
      (node (ref "J4") (pin "5") (pinfunction "5_5") (pintype "passive"))
      (node (ref "J5") (pin "2") (pinfunction "2_2") (pintype "passive"))
      (node (ref "J5") (pin "3") (pinfunction "3_3") (pintype "passive"))
      (node (ref "J5") (pin "4") (pinfunction "4_4") (pintype "passive"))
      (node (ref "J5") (pin "5") (pinfunction "5_5") (pintype "passive"))
      (node (ref "J6") (pin "2") (pinfunction "2_2") (pintype "passive"))
      (node (ref "J6") (pin "3") (pinfunction "3_3") (pintype "passive"))
      (node (ref "J6") (pin "4") (pinfunction "4_4") (pintype "passive"))
      (node (ref "J6") (pin "5") (pinfunction "5_5") (pintype "passive"))
      (node (ref "J7") (pin "2") (pinfunction "2_2") (pintype "passive"))
      (node (ref "J7") (pin "3") (pinfunction "3_3") (pintype "passive"))
      (node (ref "J7") (pin "4") (pinfunction "4_4") (pintype "passive"))
      (node (ref "J7") (pin "5") (pinfunction "5_5") (pintype "passive"))
      (node (ref "J8") (pin "2") (pinfunction "2_2") (pintype "passive"))
      (node (ref "J8") (pin "3") (pinfunction "3_3") (pintype "passive"))
      (node (ref "J8") (pin "4") (pinfunction "4_4") (pintype "passive"))
      (node (ref "J8") (pin "5") (pinfunction "5_5") (pintype "passive"))
      (node (ref "R10") (pin "1") (pinfunction "1_1") (pintype "passive"))
      (node (ref "R11") (pin "1") (pinfunction "1_1") (pintype "passive"))
      (node (ref "R2") (pin "1") (pinfunction "1_1") (pintype "passive"))
      (node (ref "R3") (pin "1") (pinfunction "1_1") (pintype "passive"))
      (node (ref "R4") (pin "1") (pinfunction "1_1") (pintype "passive"))
      (node (ref "R5") (pin "1") (pinfunction "1_1") (pintype "passive"))
      (node (ref "R7") (pin "1") (pinfunction "1_1") (pintype "passive"))
      (node (ref "R8") (pin "1") (pinfunction "1_1") (pintype "passive"))
    )
    (net (code "68") (name "Net-(IC5-START)") (class "Default")
      (node (ref "IC5") (pin "3") (pinfunction "START_3") (pintype "passive"))
      (node (ref "R6") (pin "2") (pinfunction "2_2") (pintype "passive"))
    )
    (net (code "69") (name "Net-(IC5-VREG)") (class "Default")
      (node (ref "C34") (pin "1") (pinfunction "1_1") (pintype "passive"))
      (node (ref "IC5") (pin "13") (pinfunction "VREG_13") (pintype "passive"))
    )
    (net (code "70") (name "Net-(IC6-START)") (class "Default")
      (node (ref "IC6") (pin "3") (pinfunction "START_3") (pintype "passive"))
      (node (ref "R9") (pin "2") (pinfunction "2_2") (pintype "passive"))
    )
    (net (code "71") (name "Net-(IC6-VREG)") (class "Default")
      (node (ref "C37") (pin "1") (pinfunction "1_1") (pintype "passive"))
      (node (ref "IC6") (pin "13") (pinfunction "VREG_13") (pintype "passive"))
    )
    (net (code "72") (name "Net-(IC8-I{slash}OVCC1)") (class "Default")
      (node (ref "IC8") (pin "16") (pinfunction "I/OVCC1_16") (pintype "passive"))
      (node (ref "P16") (pin "1") (pinfunction "1_1") (pintype "passive"))
    )
    (net (code "73") (name "Net-(IC8-I{slash}OVCC2)") (class "Default")
      (node (ref "IC8") (pin "15") (pinfunction "I/OVCC2_15") (pintype "passive"))
      (node (ref "P16") (pin "2") (pinfunction "2_2") (pintype "passive"))
    )
    (net (code "74") (name "Net-(IC8-I{slash}OVCC3)") (class "Default")
      (node (ref "IC8") (pin "14") (pinfunction "I/OVCC3_14") (pintype "passive"))
      (node (ref "P16") (pin "3") (pinfunction "3_3") (pintype "passive"))
    )
    (net (code "75") (name "Net-(IC8-I{slash}OVCC4)") (class "Default")
      (node (ref "IC8") (pin "11") (pinfunction "I/OVCC4_11") (pintype "passive"))
      (node (ref "P16") (pin "4") (pinfunction "4_4") (pintype "passive"))
    )
    (net (code "76") (name "Net-(IC8-I{slash}OVCC5)") (class "Default")
      (node (ref "IC8") (pin "10") (pinfunction "I/OVCC5_10") (pintype "passive"))
      (node (ref "P16") (pin "5") (pinfunction "5_5") (pintype "passive"))
    )
    (net (code "77") (name "Net-(IC8-I{slash}OVCC6)") (class "Default")
      (node (ref "IC8") (pin "9") (pinfunction "I/OVCC6_9") (pintype "passive"))
      (node (ref "P16") (pin "6") (pinfunction "6_6") (pintype "passive"))
    )
    (net (code "78") (name "VDDHV") (class "Default")
      (node (ref "C52") (pin "2") (pinfunction "2_2") (pintype "passive"))
      (node (ref "C53") (pin "2") (pinfunction "2_2") (pintype "passive"))
      (node (ref "C54") (pin "2") (pinfunction "2_2") (pintype "passive"))
      (node (ref "DUT") (pin "17") (pinfunction "VDDHV_17") (pintype "power_in"))
      (node (ref "DUT") (pin "54") (pinfunction "VDDHV_54") (pintype "power_in"))
      (node (ref "DUT") (pin "8") (pinfunction "VDDHV_8") (pintype "power_in"))
    )
    (net (code "79") (name "VDDTEST") (class "Default")
      (node (ref "C61") (pin "2") (pinfunction "2_2") (pintype "passive"))
      (node (ref "DUT") (pin "23") (pinfunction "VDDTEST_23") (pintype "power_in"))
    )
    (net (code "80") (name "unconnected-(DUT-NC-Pad3)") (class "Default")
      (node (ref "DUT") (pin "3") (pinfunction "NC_3") (pintype "passive"))
    )
    (net (code "81") (name "unconnected-(DUT-NC-Pad5)") (class "Default")
      (node (ref "DUT") (pin "5") (pinfunction "NC_5") (pintype "passive"))
    )
    (net (code "82") (name "unconnected-(DUT-NC-Pad9)") (class "Default")
      (node (ref "DUT") (pin "9") (pinfunction "NC_9") (pintype "passive"))
    )
    (net (code "83") (name "unconnected-(DUT-NC-Pad11)") (class "Default")
      (node (ref "DUT") (pin "11") (pinfunction "NC_11") (pintype "passive"))
    )
    (net (code "84") (name "unconnected-(DUT-NC-Pad14)") (class "Default")
      (node (ref "DUT") (pin "14") (pinfunction "NC_14") (pintype "passive"))
    )
    (net (code "85") (name "unconnected-(DUT-NC-Pad20)") (class "Default")
      (node (ref "DUT") (pin "20") (pinfunction "NC_20") (pintype "passive"))
    )
    (net (code "86") (name "unconnected-(DUT-NC-Pad44)") (class "Default")
      (node (ref "DUT") (pin "44") (pinfunction "NC_44") (pintype "passive"))
    )
    (net (code "87") (name "unconnected-(DUT-NC-Pad47)") (class "Default")
      (node (ref "DUT") (pin "47") (pinfunction "NC_47") (pintype "passive"))
    )
    (net (code "88") (name "unconnected-(DUT-NC-Pad49)") (class "Default")
      (node (ref "DUT") (pin "49") (pinfunction "NC_49") (pintype "passive"))
    )
    (net (code "89") (name "unconnected-(DUT-NC-Pad52)") (class "Default")
      (node (ref "DUT") (pin "52") (pinfunction "NC_52") (pintype "passive"))
    )
    (net (code "90") (name "unconnected-(DUT-NC-Pad55)") (class "Default")
      (node (ref "DUT") (pin "55") (pinfunction "NC_55") (pintype "passive"))
    )
    (net (code "91") (name "unconnected-(IC5-NC-Pad6)") (class "Default")
      (node (ref "IC5") (pin "6") (pinfunction "NC_6") (pintype "passive"))
    )
    (net (code "92") (name "unconnected-(IC6-NC-Pad6)") (class "Default")
      (node (ref "IC6") (pin "6") (pinfunction "NC_6") (pintype "passive"))
    )
    (net (code "93") (name "unconnected-(IC7-~{Q}-Pad3)") (class "Default")
      (node (ref "IC7") (pin "3") (pinfunction "~{Q}_3") (pintype "passive"))
    )
    (net (code "94") (name "unconnected-(IC9-~{Q}-Pad3)") (class "Default")
      (node (ref "IC9") (pin "3") (pinfunction "~{Q}_3") (pintype "passive"))
    )
    (net (code "95") (name "unconnected-(IC10-~{Q}-Pad3)") (class "Default")
      (node (ref "IC10") (pin "3") (pinfunction "~{Q}_3") (pintype "passive"))
    )
    (net (code "96") (name "unconnected-(IC11-~{Q}-Pad3)") (class "Default")
      (node (ref "IC11") (pin "3") (pinfunction "~{Q}_3") (pintype "passive"))
    )
    (net (code "97") (name "unconnected-(IC12-~{Q}-Pad3)") (class "Default")
      (node (ref "IC12") (pin "3") (pinfunction "~{Q}_3") (pintype "passive"))
    )
    (net (code "98") (name "unconnected-(IC13-~{Q}-Pad3)") (class "Default")
      (node (ref "IC13") (pin "3") (pinfunction "~{Q}_3") (pintype "passive"))
    )
  )
)
